# Adafruit_128x64_OLED_FeatherWing.net
KiCad netlist of a schematic drawn in EAGLE
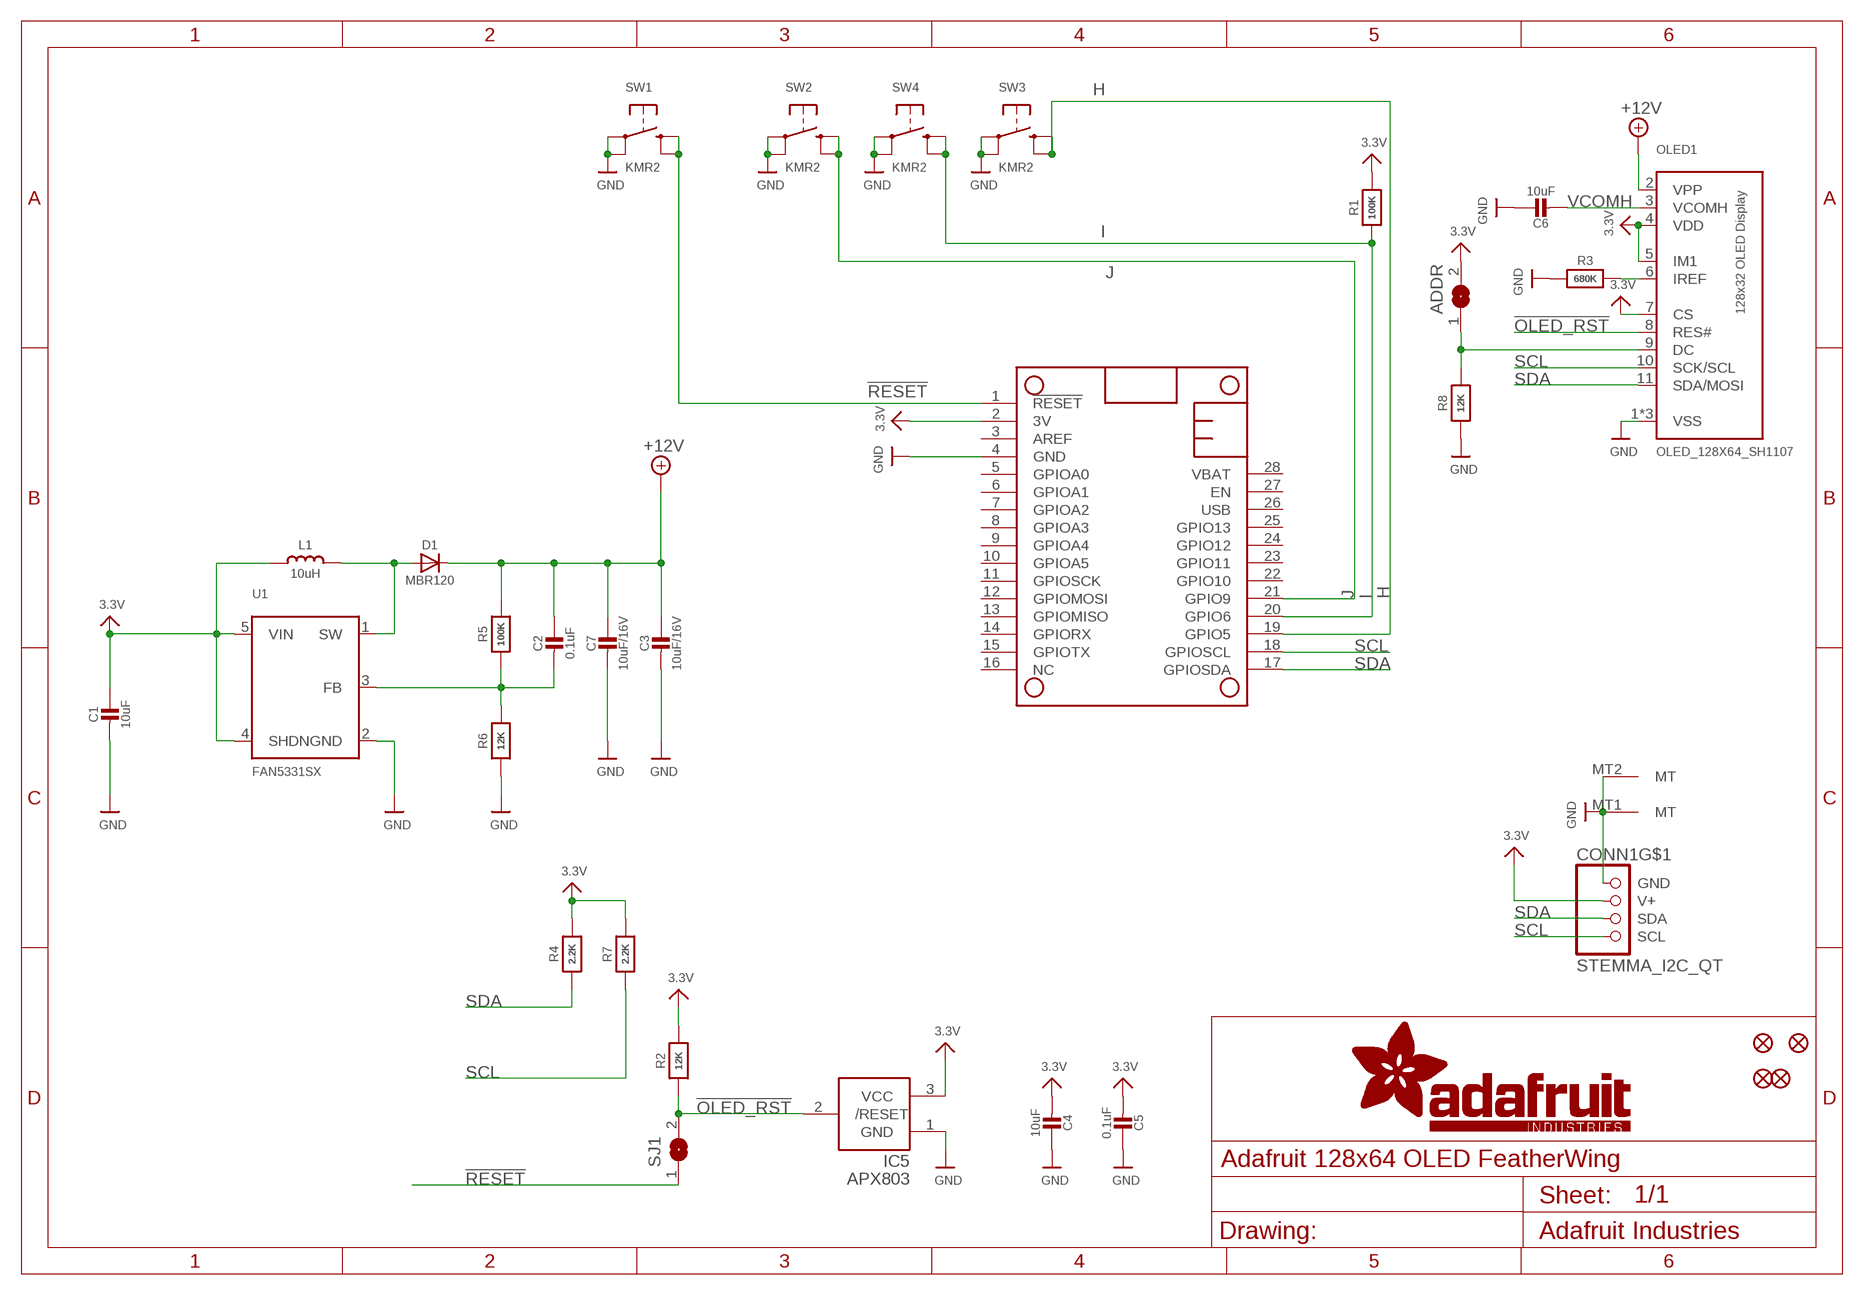
[diagram p0: schematic, sheet 1]

(export (version "E")
  (design (tool "Eeschema 10.0.6"))
  (components
    (comp (ref "ADDR")
      (value "SOLDERJUMPER")
      (footprint "eagle-import:SOLDERJUMPER_ARROW_NOPASTE")
      (libsource (lib "eagle-import") (part "SOLDERJUMPER"))
    )
    (comp (ref "C1")
      (value "10uF")
      (footprint "eagle-import:0805-NO")
      (libsource (lib "eagle-import") (part "CAP_CERAMIC0805-NOOUTLINE"))
    )
    (comp (ref "C2")
      (value "0.1uF")
      (footprint "eagle-import:0603-NO")
      (libsource (lib "eagle-import") (part "CAP_CERAMIC0603_NO"))
    )
    (comp (ref "C3")
      (value "10uF/16V")
      (footprint "eagle-import:0805-NO")
      (libsource (lib "eagle-import") (part "CAP_CERAMIC0805-NOOUTLINE"))
    )
    (comp (ref "C4")
      (value "10uF")
      (footprint "eagle-import:0805-NO")
      (libsource (lib "eagle-import") (part "CAP_CERAMIC0805-NOOUTLINE"))
    )
    (comp (ref "C5")
      (value "0.1uF")
      (footprint "eagle-import:0603-NO")
      (libsource (lib "eagle-import") (part "CAP_CERAMIC0603_NO"))
    )
    (comp (ref "C6")
      (value "10uF")
      (footprint "eagle-import:0805-NO")
      (libsource (lib "eagle-import") (part "CAP_CERAMIC0805-NOOUTLINE"))
    )
    (comp (ref "C7")
      (value "10uF/16V")
      (footprint "eagle-import:0805-NO")
      (libsource (lib "eagle-import") (part "CAP_CERAMIC0805-NOOUTLINE"))
    )
    (comp (ref "CONN1")
      (value "STEMMA_I2C_QT")
      (footprint "eagle-import:JST_SH4")
      (libsource (lib "eagle-import") (part "STEMMA_I2C_QT"))
    )
    (comp (ref "D1")
      (value "MBR120")
      (footprint "eagle-import:SOD-123")
      (libsource (lib "eagle-import") (part "DIODESOD-123"))
    )
    (comp (ref "FID1")
      (value "FIDUCIAL_1MM")
      (footprint "eagle-import:FIDUCIAL_1MM")
      (libsource (lib "eagle-import") (part "FIDUCIAL_1MM"))
    )
    (comp (ref "FID2")
      (value "FIDUCIAL_1MM")
      (footprint "eagle-import:FIDUCIAL_1MM")
      (libsource (lib "eagle-import") (part "FIDUCIAL_1MM"))
    )
    (comp (ref "FID3")
      (value "FIDUCIAL_1MM")
      (footprint "eagle-import:FIDUCIAL_1MM")
      (libsource (lib "eagle-import") (part "FIDUCIAL_1MM"))
    )
    (comp (ref "FID4")
      (value "FIDUCIAL_1MM")
      (footprint "eagle-import:FIDUCIAL_1MM")
      (libsource (lib "eagle-import") (part "FIDUCIAL_1MM"))
    )
    (comp (ref "IC5")
      (value "APX803")
      (footprint "eagle-import:SOT23")
      (libsource (lib "eagle-import") (part "AXP083-SAG"))
    )
    (comp (ref "L1")
      (value "10uH")
      (footprint "eagle-import:INDUCTOR_1007")
      (libsource (lib "eagle-import") (part "INDUCTOR"))
    )
    (comp (ref "MS1")
      (value "FEATHERWING_NODIM")
      (footprint "eagle-import:FEATHERWING_NODIM")
      (libsource (lib "eagle-import") (part "FEATHERWING_NODIM"))
    )
    (comp (ref "OLED1")
      (value "OLED_128X64_SH1107")
      (footprint "eagle-import:QT1107P11A")
      (libsource (lib "eagle-import") (part "OLED_128X64_SH1107"))
    )
    (comp (ref "R1")
      (value "100K")
      (footprint "eagle-import:0603-NO")
      (libsource (lib "eagle-import") (part "RESISTOR_0603_NOOUT"))
    )
    (comp (ref "R2")
      (value "12K")
      (footprint "eagle-import:0603-NO")
      (libsource (lib "eagle-import") (part "RESISTOR_0603_NOOUT"))
    )
    (comp (ref "R3")
      (value "680K")
      (footprint "eagle-import:0603-NO")
      (libsource (lib "eagle-import") (part "RESISTOR_0603_NOOUT"))
    )
    (comp (ref "R4")
      (value "2.2K")
      (footprint "eagle-import:0603-NO")
      (libsource (lib "eagle-import") (part "RESISTOR_0603_NOOUT"))
    )
    (comp (ref "R5")
      (value "100K")
      (footprint "eagle-import:0603-NO")
      (libsource (lib "eagle-import") (part "RESISTOR_0603_NOOUT"))
    )
    (comp (ref "R6")
      (value "12K")
      (footprint "eagle-import:0603-NO")
      (libsource (lib "eagle-import") (part "RESISTOR_0603_NOOUT"))
    )
    (comp (ref "R7")
      (value "2.2K")
      (footprint "eagle-import:0603-NO")
      (libsource (lib "eagle-import") (part "RESISTOR_0603_NOOUT"))
    )
    (comp (ref "R8")
      (value "12K")
      (footprint "eagle-import:0603-NO")
      (libsource (lib "eagle-import") (part "RESISTOR_0603_NOOUT"))
    )
    (comp (ref "SJ1")
      (value "SOLDERJUMPERCLOSED")
      (footprint "eagle-import:SOLDERJUMPER_CLOSEDWIRE")
      (libsource (lib "eagle-import") (part "SOLDERJUMPERCLOSED"))
    )
    (comp (ref "SW1")
      (value "KMR2")
      (footprint "eagle-import:BTN_KMR2_4.6X2.8")
      (libsource (lib "eagle-import") (part "SWITCH_TACT_SMT4.6X2.8"))
    )
    (comp (ref "SW2")
      (value "KMR2")
      (footprint "eagle-import:BTN_KMR2_4.6X2.8")
      (libsource (lib "eagle-import") (part "SWITCH_TACT_SMT4.6X2.8"))
    )
    (comp (ref "SW3")
      (value "KMR2")
      (footprint "eagle-import:BTN_KMR2_4.6X2.8")
      (libsource (lib "eagle-import") (part "SWITCH_TACT_SMT4.6X2.8"))
    )
    (comp (ref "SW4")
      (value "KMR2")
      (footprint "eagle-import:BTN_KMR2_4.6X2.8")
      (libsource (lib "eagle-import") (part "SWITCH_TACT_SMT4.6X2.8"))
    )
    (comp (ref "U1")
      (value "FAN5331SX")
      (footprint "eagle-import:SOT23-5")
      (libsource (lib "eagle-import") (part "VREG_FAN5331"))
    )
  )
  (nets
    (net (code "1") (name "+12V") (class "Default")
      (node (ref "C2") (pin "1") (pinfunction "1_1") (pintype "passive"))
      (node (ref "C3") (pin "1") (pinfunction "1_1") (pintype "passive"))
      (node (ref "C7") (pin "1") (pinfunction "1_1") (pintype "passive"))
      (node (ref "D1") (pin "C") (pinfunction "C_C") (pintype "passive"))
      (node (ref "OLED1") (pin "2") (pinfunction "VPP_2") (pintype "power_in"))
      (node (ref "R5") (pin "2") (pinfunction "2_2") (pintype "passive"))
    )
    (net (code "2") (name "/H") (class "Default")
      (node (ref "MS1") (pin "19") (pinfunction "GPIO5_19") (pintype "bidirectional"))
      (node (ref "SW3") (pin "B") (pinfunction "S_B") (pintype "passive"))
      (node (ref "SW3") (pin "B'") (pinfunction "S1_B'") (pintype "passive"))
    )
    (net (code "3") (name "/I") (class "Default")
      (node (ref "MS1") (pin "20") (pinfunction "GPIO6_20") (pintype "bidirectional"))
      (node (ref "R1") (pin "1") (pinfunction "1_1") (pintype "passive"))
      (node (ref "SW4") (pin "B") (pinfunction "S_B") (pintype "passive"))
      (node (ref "SW4") (pin "B'") (pinfunction "S1_B'") (pintype "passive"))
    )
    (net (code "4") (name "/J") (class "Default")
      (node (ref "MS1") (pin "21") (pinfunction "GPIO9_21") (pintype "bidirectional"))
      (node (ref "SW2") (pin "B") (pinfunction "S_B") (pintype "passive"))
      (node (ref "SW2") (pin "B'") (pinfunction "S1_B'") (pintype "passive"))
    )
    (net (code "5") (name "/SCL") (class "Default")
      (node (ref "CONN1") (pin "4") (pinfunction "SCL_4") (pintype "passive"))
      (node (ref "MS1") (pin "18") (pinfunction "GPIOSCL_18") (pintype "bidirectional"))
      (node (ref "OLED1") (pin "10") (pinfunction "SCK/SCL_10") (pintype "input"))
      (node (ref "R7") (pin "1") (pinfunction "1_1") (pintype "passive"))
    )
    (net (code "6") (name "/SDA") (class "Default")
      (node (ref "CONN1") (pin "3") (pinfunction "SDA_3") (pintype "passive"))
      (node (ref "MS1") (pin "17") (pinfunction "GPIOSDA_17") (pintype "bidirectional"))
      (node (ref "OLED1") (pin "11") (pinfunction "SDA/MOSI_11") (pintype "input"))
      (node (ref "R4") (pin "1") (pinfunction "1_1") (pintype "passive"))
    )
    (net (code "7") (name "/USB") (class "Default")
      (node (ref "MS1") (pin "26") (pinfunction "USB_26") (pintype "power_in"))
    )
    (net (code "8") (name "/VBAT") (class "Default")
      (node (ref "MS1") (pin "28") (pinfunction "VBAT_28") (pintype "power_in"))
    )
    (net (code "9") (name "/VCOMH") (class "Default")
      (node (ref "C6") (pin "2") (pinfunction "2_2") (pintype "passive"))
      (node (ref "OLED1") (pin "3") (pinfunction "VCOMH_3") (pintype "power_in"))
    )
    (net (code "10") (name "/~{OLED_RST}") (class "Default")
      (node (ref "IC5") (pin "2") (pinfunction "/RESET_2") (pintype "output"))
      (node (ref "OLED1") (pin "8") (pinfunction "RES#_8") (pintype "input"))
      (node (ref "R2") (pin "1") (pinfunction "1_1") (pintype "passive"))
      (node (ref "SJ1") (pin "2") (pinfunction "2_2") (pintype "passive"))
    )
    (net (code "11") (name "/~{RESET}") (class "Default")
      (node (ref "MS1") (pin "1") (pinfunction "~{RESET}_1") (pintype "input"))
      (node (ref "SJ1") (pin "1") (pinfunction "1_1") (pintype "passive"))
      (node (ref "SW1") (pin "B") (pinfunction "S_B") (pintype "passive"))
      (node (ref "SW1") (pin "B'") (pinfunction "S1_B'") (pintype "passive"))
    )
    (net (code "12") (name "3.3V") (class "Default")
      (node (ref "ADDR") (pin "2") (pinfunction "2_2") (pintype "passive"))
      (node (ref "C1") (pin "1") (pinfunction "1_1") (pintype "passive"))
      (node (ref "C4") (pin "2") (pinfunction "2_2") (pintype "passive"))
      (node (ref "C5") (pin "2") (pinfunction "2_2") (pintype "passive"))
      (node (ref "CONN1") (pin "2") (pinfunction "V+_2") (pintype "passive"))
      (node (ref "IC5") (pin "3") (pinfunction "VCC_3") (pintype "power_in"))
      (node (ref "L1") (pin "P$1") (pinfunction "1_P$1") (pintype "passive"))
      (node (ref "MS1") (pin "2") (pinfunction "3V_2") (pintype "power_in"))
      (node (ref "OLED1") (pin "4") (pinfunction "VDD_4") (pintype "power_in"))
      (node (ref "OLED1") (pin "5") (pinfunction "IM1_5") (pintype "input"))
      (node (ref "OLED1") (pin "7") (pinfunction "CS_7") (pintype "input"))
      (node (ref "R1") (pin "2") (pinfunction "2_2") (pintype "passive"))
      (node (ref "R2") (pin "2") (pinfunction "2_2") (pintype "passive"))
      (node (ref "R4") (pin "2") (pinfunction "2_2") (pintype "passive"))
      (node (ref "R7") (pin "2") (pinfunction "2_2") (pintype "passive"))
      (node (ref "U1") (pin "4") (pinfunction "SHDN_4") (pintype "bidirectional"))
      (node (ref "U1") (pin "5") (pinfunction "VIN_5") (pintype "bidirectional"))
    )
    (net (code "13") (name "GND") (class "Default")
      (node (ref "C1") (pin "2") (pinfunction "2_2") (pintype "passive"))
      (node (ref "C3") (pin "2") (pinfunction "2_2") (pintype "passive"))
      (node (ref "C4") (pin "1") (pinfunction "1_1") (pintype "passive"))
      (node (ref "C5") (pin "1") (pinfunction "1_1") (pintype "passive"))
      (node (ref "C6") (pin "1") (pinfunction "1_1") (pintype "passive"))
      (node (ref "C7") (pin "2") (pinfunction "2_2") (pintype "passive"))
      (node (ref "CONN1") (pin "1") (pinfunction "GND_1") (pintype "passive"))
      (node (ref "CONN1") (pin "MT1") (pinfunction "MT_MT1") (pintype "bidirectional"))
      (node (ref "CONN1") (pin "MT2") (pinfunction "MT_MT2") (pintype "bidirectional"))
      (node (ref "IC5") (pin "1") (pinfunction "GND_1") (pintype "power_in"))
      (node (ref "MS1") (pin "4") (pinfunction "GND_4") (pintype "power_in"))
      (node (ref "OLED1") (pin "1") (pinfunction "VSS_1") (pintype "power_in"))
      (node (ref "OLED1") (pin "12") (pinfunction "VSS_12") (pintype "power_in"))
      (node (ref "OLED1") (pin "13") (pinfunction "VSS_13") (pintype "power_in"))
      (node (ref "R3") (pin "1") (pinfunction "1_1") (pintype "passive"))
      (node (ref "R6") (pin "1") (pinfunction "1_1") (pintype "passive"))
      (node (ref "R8") (pin "1") (pinfunction "1_1") (pintype "passive"))
      (node (ref "SW1") (pin "A") (pinfunction "P_A") (pintype "passive"))
      (node (ref "SW1") (pin "A'") (pinfunction "P1_A'") (pintype "passive"))
      (node (ref "SW2") (pin "A") (pinfunction "P_A") (pintype "passive"))
      (node (ref "SW2") (pin "A'") (pinfunction "P1_A'") (pintype "passive"))
      (node (ref "SW3") (pin "A") (pinfunction "P_A") (pintype "passive"))
      (node (ref "SW3") (pin "A'") (pinfunction "P1_A'") (pintype "passive"))
      (node (ref "SW4") (pin "A") (pinfunction "P_A") (pintype "passive"))
      (node (ref "SW4") (pin "A'") (pinfunction "P1_A'") (pintype "passive"))
      (node (ref "U1") (pin "2") (pinfunction "GND_2") (pintype "bidirectional"))
    )
    (net (code "14") (name "Net-(L1-2)") (class "Default")
      (node (ref "D1") (pin "A") (pinfunction "A_A") (pintype "passive"))
      (node (ref "L1") (pin "P$2") (pinfunction "2_P$2") (pintype "passive"))
      (node (ref "U1") (pin "1") (pinfunction "SW_1") (pintype "bidirectional"))
    )
    (net (code "15") (name "Net-(OLED1-DC)") (class "Default")
      (node (ref "ADDR") (pin "1") (pinfunction "1_1") (pintype "passive"))
      (node (ref "OLED1") (pin "9") (pinfunction "DC_9") (pintype "input"))
      (node (ref "R8") (pin "2") (pinfunction "2_2") (pintype "passive"))
    )
    (net (code "16") (name "Net-(OLED1-IREF)") (class "Default")
      (node (ref "OLED1") (pin "6") (pinfunction "IREF_6") (pintype "bidirectional"))
      (node (ref "R3") (pin "2") (pinfunction "2_2") (pintype "passive"))
    )
    (net (code "17") (name "Net-(U1-FB)") (class "Default")
      (node (ref "C2") (pin "2") (pinfunction "2_2") (pintype "passive"))
      (node (ref "R5") (pin "1") (pinfunction "1_1") (pintype "passive"))
      (node (ref "R6") (pin "2") (pinfunction "2_2") (pintype "passive"))
      (node (ref "U1") (pin "3") (pinfunction "FB_3") (pintype "bidirectional"))
    )
    (net (code "18") (name "unconnected-(MS1-AREF-Pad3)") (class "Default")
      (node (ref "MS1") (pin "3") (pinfunction "AREF_3") (pintype "passive"))
    )
    (net (code "19") (name "unconnected-(MS1-EN-Pad27)") (class "Default")
      (node (ref "MS1") (pin "27") (pinfunction "EN_27") (pintype "passive"))
    )
    (net (code "20") (name "unconnected-(MS1-GPIO10-Pad22)") (class "Default")
      (node (ref "MS1") (pin "22") (pinfunction "GPIO10_22") (pintype "bidirectional"))
    )
    (net (code "21") (name "unconnected-(MS1-GPIO11-Pad23)") (class "Default")
      (node (ref "MS1") (pin "23") (pinfunction "GPIO11_23") (pintype "bidirectional"))
    )
    (net (code "22") (name "unconnected-(MS1-GPIO12-Pad24)") (class "Default")
      (node (ref "MS1") (pin "24") (pinfunction "GPIO12_24") (pintype "bidirectional"))
    )
    (net (code "23") (name "unconnected-(MS1-GPIO13-Pad25)") (class "Default")
      (node (ref "MS1") (pin "25") (pinfunction "GPIO13_25") (pintype "bidirectional"))
    )
    (net (code "24") (name "unconnected-(MS1-GPIOA0-Pad5)") (class "Default")
      (node (ref "MS1") (pin "5") (pinfunction "GPIOA0_5") (pintype "bidirectional"))
    )
    (net (code "25") (name "unconnected-(MS1-GPIOA1-Pad6)") (class "Default")
      (node (ref "MS1") (pin "6") (pinfunction "GPIOA1_6") (pintype "bidirectional"))
    )
    (net (code "26") (name "unconnected-(MS1-GPIOA2-Pad7)") (class "Default")
      (node (ref "MS1") (pin "7") (pinfunction "GPIOA2_7") (pintype "bidirectional"))
    )
    (net (code "27") (name "unconnected-(MS1-GPIOA3-Pad8)") (class "Default")
      (node (ref "MS1") (pin "8") (pinfunction "GPIOA3_8") (pintype "bidirectional"))
    )
    (net (code "28") (name "unconnected-(MS1-GPIOA4-Pad9)") (class "Default")
      (node (ref "MS1") (pin "9") (pinfunction "GPIOA4_9") (pintype "bidirectional"))
    )
    (net (code "29") (name "unconnected-(MS1-GPIOA5-Pad10)") (class "Default")
      (node (ref "MS1") (pin "10") (pinfunction "GPIOA5_10") (pintype "bidirectional"))
    )
    (net (code "30") (name "unconnected-(MS1-GPIOMISO-Pad13)") (class "Default")
      (node (ref "MS1") (pin "13") (pinfunction "GPIOMISO_13") (pintype "bidirectional"))
    )
    (net (code "31") (name "unconnected-(MS1-GPIOMOSI-Pad12)") (class "Default")
      (node (ref "MS1") (pin "12") (pinfunction "GPIOMOSI_12") (pintype "bidirectional"))
    )
    (net (code "32") (name "unconnected-(MS1-GPIORX-Pad14)") (class "Default")
      (node (ref "MS1") (pin "14") (pinfunction "GPIORX_14") (pintype "bidirectional"))
    )
    (net (code "33") (name "unconnected-(MS1-GPIOSCK-Pad11)") (class "Default")
      (node (ref "MS1") (pin "11") (pinfunction "GPIOSCK_11") (pintype "bidirectional"))
    )
    (net (code "34") (name "unconnected-(MS1-GPIOTX-Pad15)") (class "Default")
      (node (ref "MS1") (pin "15") (pinfunction "GPIOTX_15") (pintype "bidirectional"))
    )
    (net (code "35") (name "unconnected-(MS1-NC-Pad16)") (class "Default")
      (node (ref "MS1") (pin "16") (pinfunction "NC_16") (pintype "passive"))
    )
  )
)
